# 00A-006.net
KiCad netlist of a schematic drawn in EAGLE
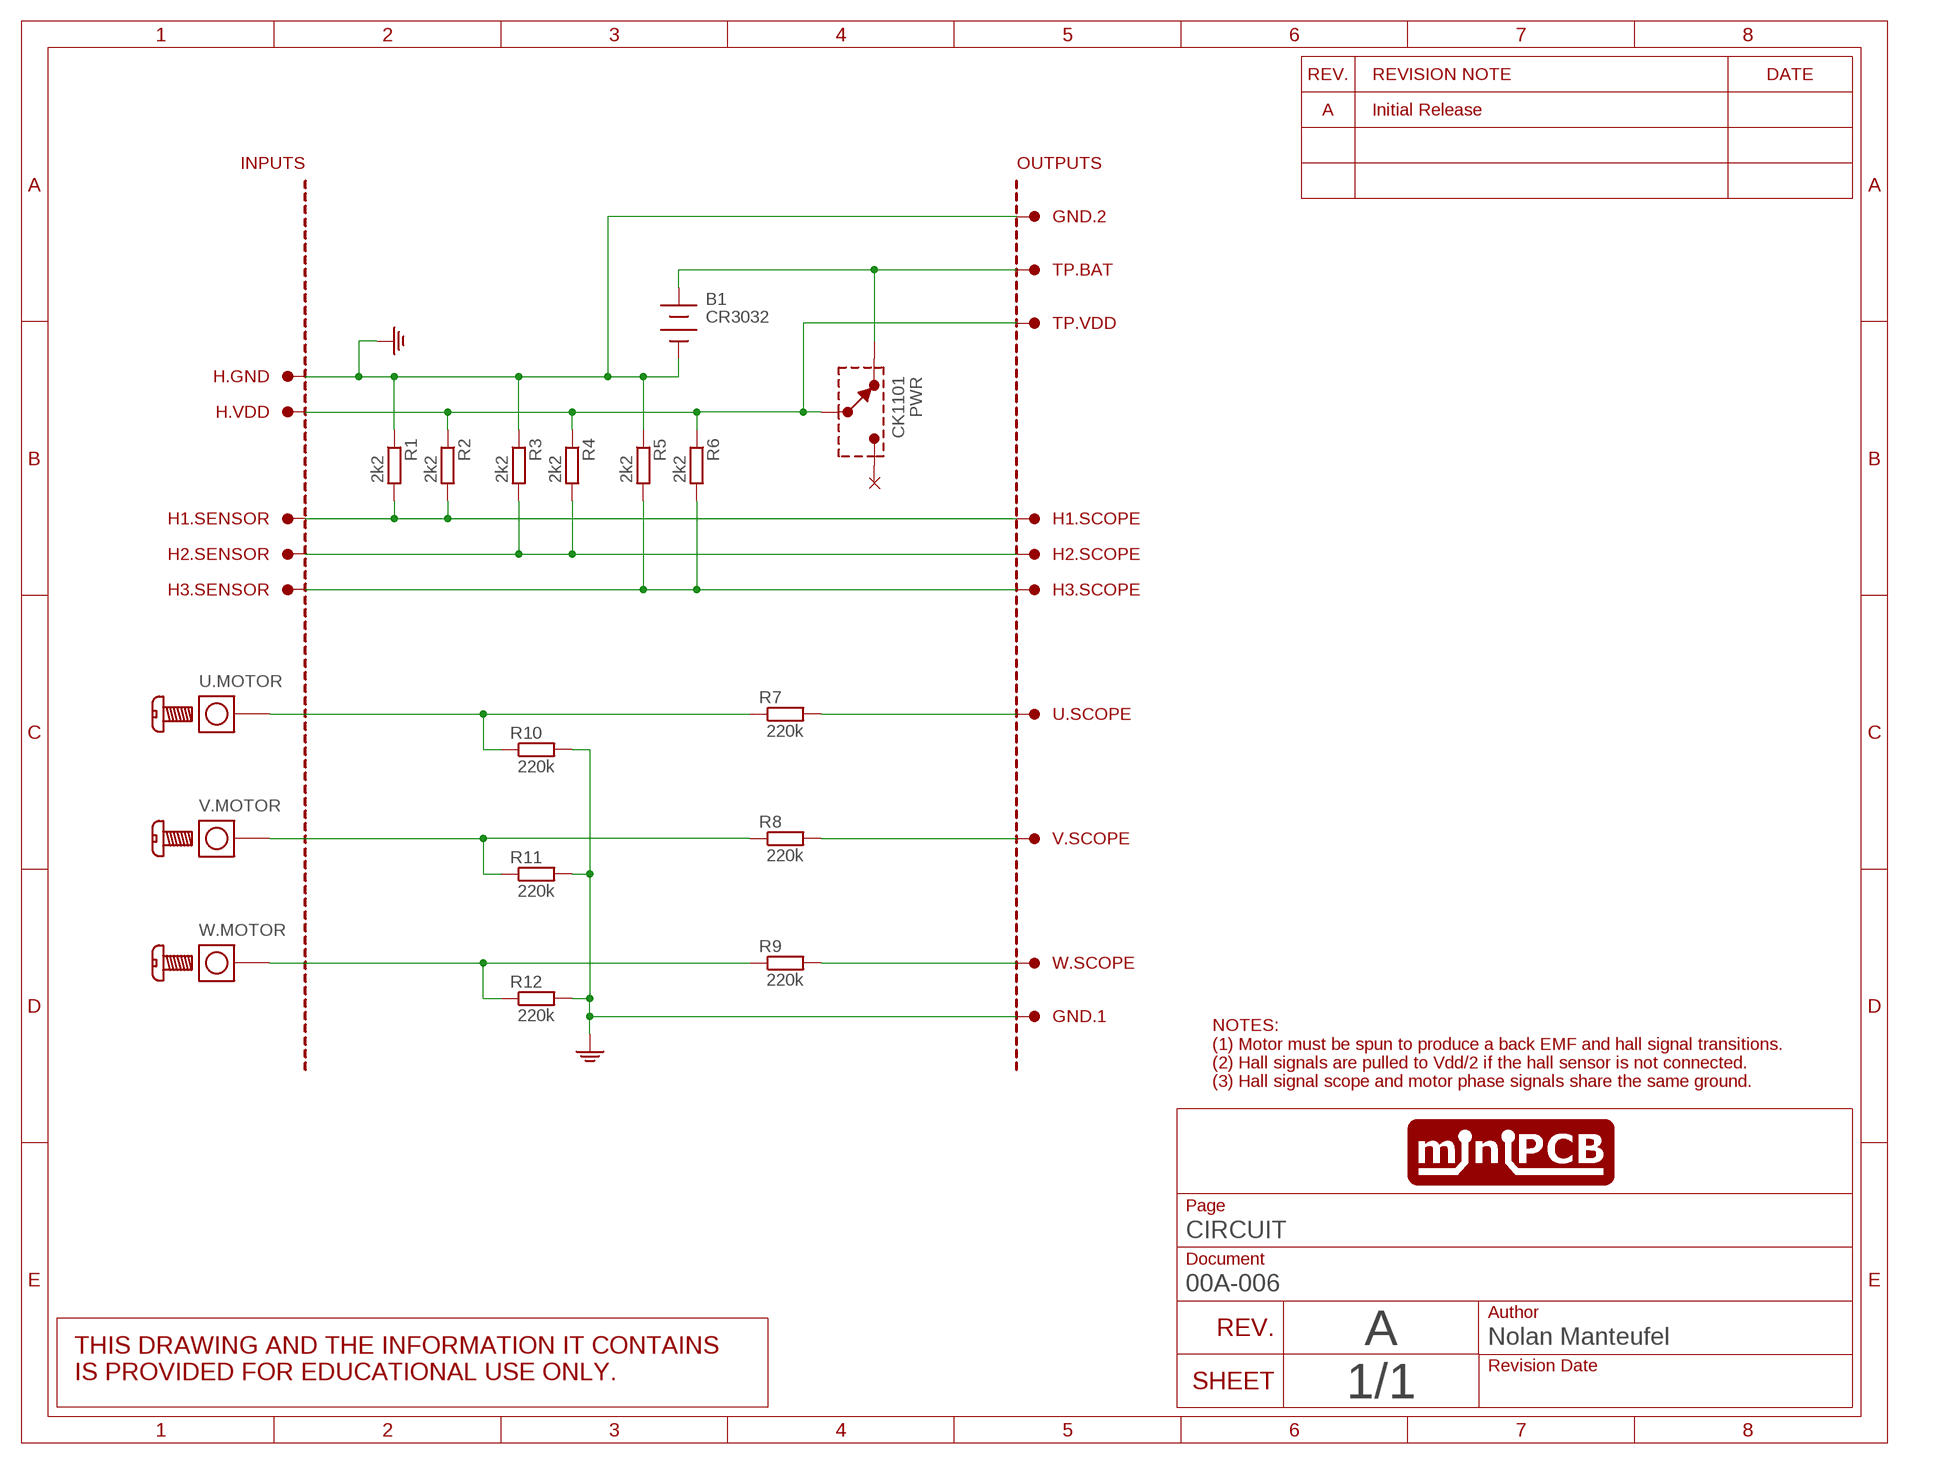
[diagram p0: schematic, sheet 1]

(export (version "E")
  (design (tool "Eeschema 10.0.6"))
  (components
    (comp (ref "B1")
      (value "CR3032")
      (footprint "eagle-import:BATTERY-CR3032-KE3034")
      (libsource (lib "eagle-import") (part "BATTERYKE3034"))
    )
    (comp (ref "GND.1")
      (value "TESTPOINTKE5000")
      (footprint "eagle-import:PINS_1_TESTPOINT_KE5000")
      (libsource (lib "eagle-import") (part "TESTPOINTKE5000"))
    )
    (comp (ref "GND.2")
      (value "TESTPOINTKE5000")
      (footprint "eagle-import:PINS_1_TESTPOINT_KE5000")
      (libsource (lib "eagle-import") (part "TESTPOINTKE5000"))
    )
    (comp (ref "H.GND")
      (value "GND")
      (footprint "eagle-import:PINS_1_1MM")
      (libsource (lib "eagle-import") (part "TESTPOINT24AWG"))
    )
    (comp (ref "H.VDD")
      (value "VDD")
      (footprint "eagle-import:PINS_1_1MM")
      (libsource (lib "eagle-import") (part "TESTPOINT24AWG"))
    )
    (comp (ref "H1.SCOPE")
      (value "TESTPOINTKE5000")
      (footprint "eagle-import:PINS_1_TESTPOINT_KE5000")
      (libsource (lib "eagle-import") (part "TESTPOINTKE5000"))
    )
    (comp (ref "H1.SENSOR")
      (value "H1")
      (footprint "eagle-import:PINS_1_1MM")
      (libsource (lib "eagle-import") (part "TESTPOINT24AWG"))
    )
    (comp (ref "H2.SCOPE")
      (value "TESTPOINTKE5000")
      (footprint "eagle-import:PINS_1_TESTPOINT_KE5000")
      (libsource (lib "eagle-import") (part "TESTPOINTKE5000"))
    )
    (comp (ref "H2.SENSOR")
      (value "H2")
      (footprint "eagle-import:PINS_1_1MM")
      (libsource (lib "eagle-import") (part "TESTPOINT24AWG"))
    )
    (comp (ref "H3.SCOPE")
      (value "TESTPOINTKE5000")
      (footprint "eagle-import:PINS_1_TESTPOINT_KE5000")
      (libsource (lib "eagle-import") (part "TESTPOINTKE5000"))
    )
    (comp (ref "H3.SENSOR")
      (value "H3")
      (footprint "eagle-import:PINS_1_1MM")
      (libsource (lib "eagle-import") (part "TESTPOINT24AWG"))
    )
    (comp (ref "PWR")
      (value "CK1101")
      (footprint "eagle-import:CK1101")
      (libsource (lib "eagle-import") (part "SPDTM2S3CQE2"))
    )
    (comp (ref "R1")
      (value "2k2")
      (footprint "eagle-import:R0805")
      (libsource (lib "eagle-import") (part "RESISTORSMD"))
    )
    (comp (ref "R2")
      (value "2k2")
      (footprint "eagle-import:R0805")
      (libsource (lib "eagle-import") (part "RESISTORSMD"))
    )
    (comp (ref "R3")
      (value "2k2")
      (footprint "eagle-import:R0805")
      (libsource (lib "eagle-import") (part "RESISTORSMD"))
    )
    (comp (ref "R4")
      (value "2k2")
      (footprint "eagle-import:R0805")
      (libsource (lib "eagle-import") (part "RESISTORSMD"))
    )
    (comp (ref "R5")
      (value "2k2")
      (footprint "eagle-import:R0805")
      (libsource (lib "eagle-import") (part "RESISTORSMD"))
    )
    (comp (ref "R6")
      (value "2k2")
      (footprint "eagle-import:R0805")
      (libsource (lib "eagle-import") (part "RESISTORSMD"))
    )
    (comp (ref "R7")
      (value "220k")
      (footprint "eagle-import:R0805")
      (libsource (lib "eagle-import") (part "RESISTORSMD"))
    )
    (comp (ref "R8")
      (value "220k")
      (footprint "eagle-import:R0805")
      (libsource (lib "eagle-import") (part "RESISTORSMD"))
    )
    (comp (ref "R9")
      (value "220k")
      (footprint "eagle-import:R0805")
      (libsource (lib "eagle-import") (part "RESISTORSMD"))
    )
    (comp (ref "R10")
      (value "220k")
      (footprint "eagle-import:R0805")
      (libsource (lib "eagle-import") (part "RESISTORSMD"))
    )
    (comp (ref "R11")
      (value "220k")
      (footprint "eagle-import:R0805")
      (libsource (lib "eagle-import") (part "RESISTORSMD"))
    )
    (comp (ref "R12")
      (value "220k")
      (footprint "eagle-import:R0805")
      (libsource (lib "eagle-import") (part "RESISTORSMD"))
    )
    (comp (ref "TP.BAT")
      (value "TESTPOINTKE5000-SMTEXT")
      (footprint "eagle-import:PINS_1_TESTPOINT_KE5000_NOTEXT")
      (libsource (lib "eagle-import") (part "TESTPOINTKE5000-SMTEXT"))
    )
    (comp (ref "TP.VDD")
      (value "TESTPOINTKE5000-SMTEXT")
      (footprint "eagle-import:PINS_1_TESTPOINT_KE5000_NOTEXT")
      (libsource (lib "eagle-import") (part "TESTPOINTKE5000-SMTEXT"))
    )
    (comp (ref "U$1")
      (value "MINIPCB_0P50X100")
      (footprint "eagle-import:MINIPCB_0P_50X100")
      (fields (field (name "PART_NUMBER") "#00A-006"))
      (libsource (lib "eagle-import") (part "MINIPCB_0P50X100"))
    )
    (comp (ref "U.MOTOR")
      (value "SCREW-TERMINAL")
      (footprint "eagle-import:SCREW-TERMINAL-M3")
      (libsource (lib "eagle-import") (part "SCREW-TERMINAL"))
    )
    (comp (ref "U.SCOPE")
      (value "TESTPOINTKE5000")
      (footprint "eagle-import:PINS_1_TESTPOINT_KE5000")
      (libsource (lib "eagle-import") (part "TESTPOINTKE5000"))
    )
    (comp (ref "V.MOTOR")
      (value "SCREW-TERMINAL")
      (footprint "eagle-import:SCREW-TERMINAL-M3")
      (libsource (lib "eagle-import") (part "SCREW-TERMINAL"))
    )
    (comp (ref "V.SCOPE")
      (value "TESTPOINTKE5000")
      (footprint "eagle-import:PINS_1_TESTPOINT_KE5000")
      (libsource (lib "eagle-import") (part "TESTPOINTKE5000"))
    )
    (comp (ref "W.MOTOR")
      (value "SCREW-TERMINAL")
      (footprint "eagle-import:SCREW-TERMINAL-M3")
      (libsource (lib "eagle-import") (part "SCREW-TERMINAL"))
    )
    (comp (ref "W.SCOPE")
      (value "TESTPOINTKE5000")
      (footprint "eagle-import:PINS_1_TESTPOINT_KE5000")
      (libsource (lib "eagle-import") (part "TESTPOINTKE5000"))
    )
  )
  (nets
    (net (code "1") (name "GND") (class "Default")
      (node (ref "B1") (pin "3-") (pinfunction "-_3-") (pintype "bidirectional"))
      (node (ref "GND.1") (pin "1") (pinfunction "1_1") (pintype "bidirectional"))
      (node (ref "GND.2") (pin "1") (pinfunction "1_1") (pintype "bidirectional"))
      (node (ref "H.GND") (pin "1") (pinfunction "1_1") (pintype "bidirectional"))
      (node (ref "H.GND") (pin "2") (pinfunction "1_2") (pintype "bidirectional"))
      (node (ref "R1") (pin "1") (pinfunction "1_1") (pintype "passive"))
      (node (ref "R10") (pin "2") (pinfunction "2_2") (pintype "passive"))
      (node (ref "R11") (pin "2") (pinfunction "2_2") (pintype "passive"))
      (node (ref "R12") (pin "2") (pinfunction "2_2") (pintype "passive"))
      (node (ref "R3") (pin "1") (pinfunction "1_1") (pintype "passive"))
      (node (ref "R5") (pin "1") (pinfunction "1_1") (pintype "passive"))
    )
    (net (code "2") (name "Net-(H1.SCOPE-Pad1)") (class "Default")
      (node (ref "H1.SCOPE") (pin "1") (pinfunction "1_1") (pintype "bidirectional"))
      (node (ref "H1.SENSOR") (pin "1") (pinfunction "1_1") (pintype "bidirectional"))
      (node (ref "H1.SENSOR") (pin "2") (pinfunction "1_2") (pintype "bidirectional"))
      (node (ref "R1") (pin "2") (pinfunction "2_2") (pintype "passive"))
      (node (ref "R2") (pin "2") (pinfunction "2_2") (pintype "passive"))
    )
    (net (code "3") (name "Net-(H2.SCOPE-Pad1)") (class "Default")
      (node (ref "H2.SCOPE") (pin "1") (pinfunction "1_1") (pintype "bidirectional"))
      (node (ref "H2.SENSOR") (pin "1") (pinfunction "1_1") (pintype "bidirectional"))
      (node (ref "H2.SENSOR") (pin "2") (pinfunction "1_2") (pintype "bidirectional"))
      (node (ref "R3") (pin "2") (pinfunction "2_2") (pintype "passive"))
      (node (ref "R4") (pin "2") (pinfunction "2_2") (pintype "passive"))
    )
    (net (code "4") (name "Net-(H3.SCOPE-Pad1)") (class "Default")
      (node (ref "H3.SCOPE") (pin "1") (pinfunction "1_1") (pintype "bidirectional"))
      (node (ref "H3.SENSOR") (pin "1") (pinfunction "1_1") (pintype "bidirectional"))
      (node (ref "H3.SENSOR") (pin "2") (pinfunction "1_2") (pintype "bidirectional"))
      (node (ref "R5") (pin "2") (pinfunction "2_2") (pintype "passive"))
      (node (ref "R6") (pin "2") (pinfunction "2_2") (pintype "passive"))
    )
    (net (code "5") (name "Net-(PWR-1)") (class "Default")
      (node (ref "B1") (pin "1+") (pinfunction "+_1+") (pintype "bidirectional"))
      (node (ref "B1") (pin "2+") (pinfunction "+_2+") (pintype "bidirectional"))
      (node (ref "PWR") (pin "P$1") (pinfunction "1_P$1") (pintype "bidirectional"))
      (node (ref "TP.BAT") (pin "1") (pinfunction "1_1") (pintype "bidirectional"))
    )
    (net (code "6") (name "Net-(PWR-2)") (class "Default")
      (node (ref "H.VDD") (pin "1") (pinfunction "1_1") (pintype "bidirectional"))
      (node (ref "H.VDD") (pin "2") (pinfunction "1_2") (pintype "bidirectional"))
      (node (ref "PWR") (pin "P$2") (pinfunction "2_P$2") (pintype "bidirectional"))
      (node (ref "R2") (pin "1") (pinfunction "1_1") (pintype "passive"))
      (node (ref "R4") (pin "1") (pinfunction "1_1") (pintype "passive"))
      (node (ref "R6") (pin "1") (pinfunction "1_1") (pintype "passive"))
      (node (ref "TP.VDD") (pin "1") (pinfunction "1_1") (pintype "bidirectional"))
    )
    (net (code "7") (name "Net-(R7-Pad2)") (class "Default")
      (node (ref "R7") (pin "2") (pinfunction "2_2") (pintype "passive"))
      (node (ref "U.SCOPE") (pin "1") (pinfunction "1_1") (pintype "bidirectional"))
    )
    (net (code "8") (name "Net-(R8-Pad2)") (class "Default")
      (node (ref "R8") (pin "2") (pinfunction "2_2") (pintype "passive"))
      (node (ref "V.SCOPE") (pin "1") (pinfunction "1_1") (pintype "bidirectional"))
    )
    (net (code "9") (name "Net-(R9-Pad2)") (class "Default")
      (node (ref "R9") (pin "2") (pinfunction "2_2") (pintype "passive"))
      (node (ref "W.SCOPE") (pin "1") (pinfunction "1_1") (pintype "bidirectional"))
    )
    (net (code "10") (name "Net-(R10-Pad1)") (class "Default")
      (node (ref "R10") (pin "1") (pinfunction "1_1") (pintype "passive"))
      (node (ref "R7") (pin "1") (pinfunction "1_1") (pintype "passive"))
      (node (ref "U.MOTOR") (pin "1") (pinfunction "1_1") (pintype "bidirectional"))
      (node (ref "U.MOTOR") (pin "2") (pinfunction "1_2") (pintype "bidirectional"))
      (node (ref "U.MOTOR") (pin "3") (pinfunction "1_3") (pintype "bidirectional"))
      (node (ref "U.MOTOR") (pin "4") (pinfunction "1_4") (pintype "bidirectional"))
    )
    (net (code "11") (name "Net-(R11-Pad1)") (class "Default")
      (node (ref "R11") (pin "1") (pinfunction "1_1") (pintype "passive"))
      (node (ref "R8") (pin "1") (pinfunction "1_1") (pintype "passive"))
      (node (ref "V.MOTOR") (pin "1") (pinfunction "1_1") (pintype "bidirectional"))
      (node (ref "V.MOTOR") (pin "2") (pinfunction "1_2") (pintype "bidirectional"))
      (node (ref "V.MOTOR") (pin "3") (pinfunction "1_3") (pintype "bidirectional"))
      (node (ref "V.MOTOR") (pin "4") (pinfunction "1_4") (pintype "bidirectional"))
    )
    (net (code "12") (name "Net-(R12-Pad1)") (class "Default")
      (node (ref "R12") (pin "1") (pinfunction "1_1") (pintype "passive"))
      (node (ref "R9") (pin "1") (pinfunction "1_1") (pintype "passive"))
      (node (ref "W.MOTOR") (pin "1") (pinfunction "1_1") (pintype "bidirectional"))
      (node (ref "W.MOTOR") (pin "2") (pinfunction "1_2") (pintype "bidirectional"))
      (node (ref "W.MOTOR") (pin "3") (pinfunction "1_3") (pintype "bidirectional"))
      (node (ref "W.MOTOR") (pin "4") (pinfunction "1_4") (pintype "bidirectional"))
    )
    (net (code "13") (name "unconnected-(PWR-3-PadP$3)") (class "Default")
      (node (ref "PWR") (pin "P$3") (pinfunction "3_P$3") (pintype "bidirectional"))
    )
  )
)
